# woodenHaptics_v_0_4.net
KiCad netlist of a schematic drawn in EAGLE
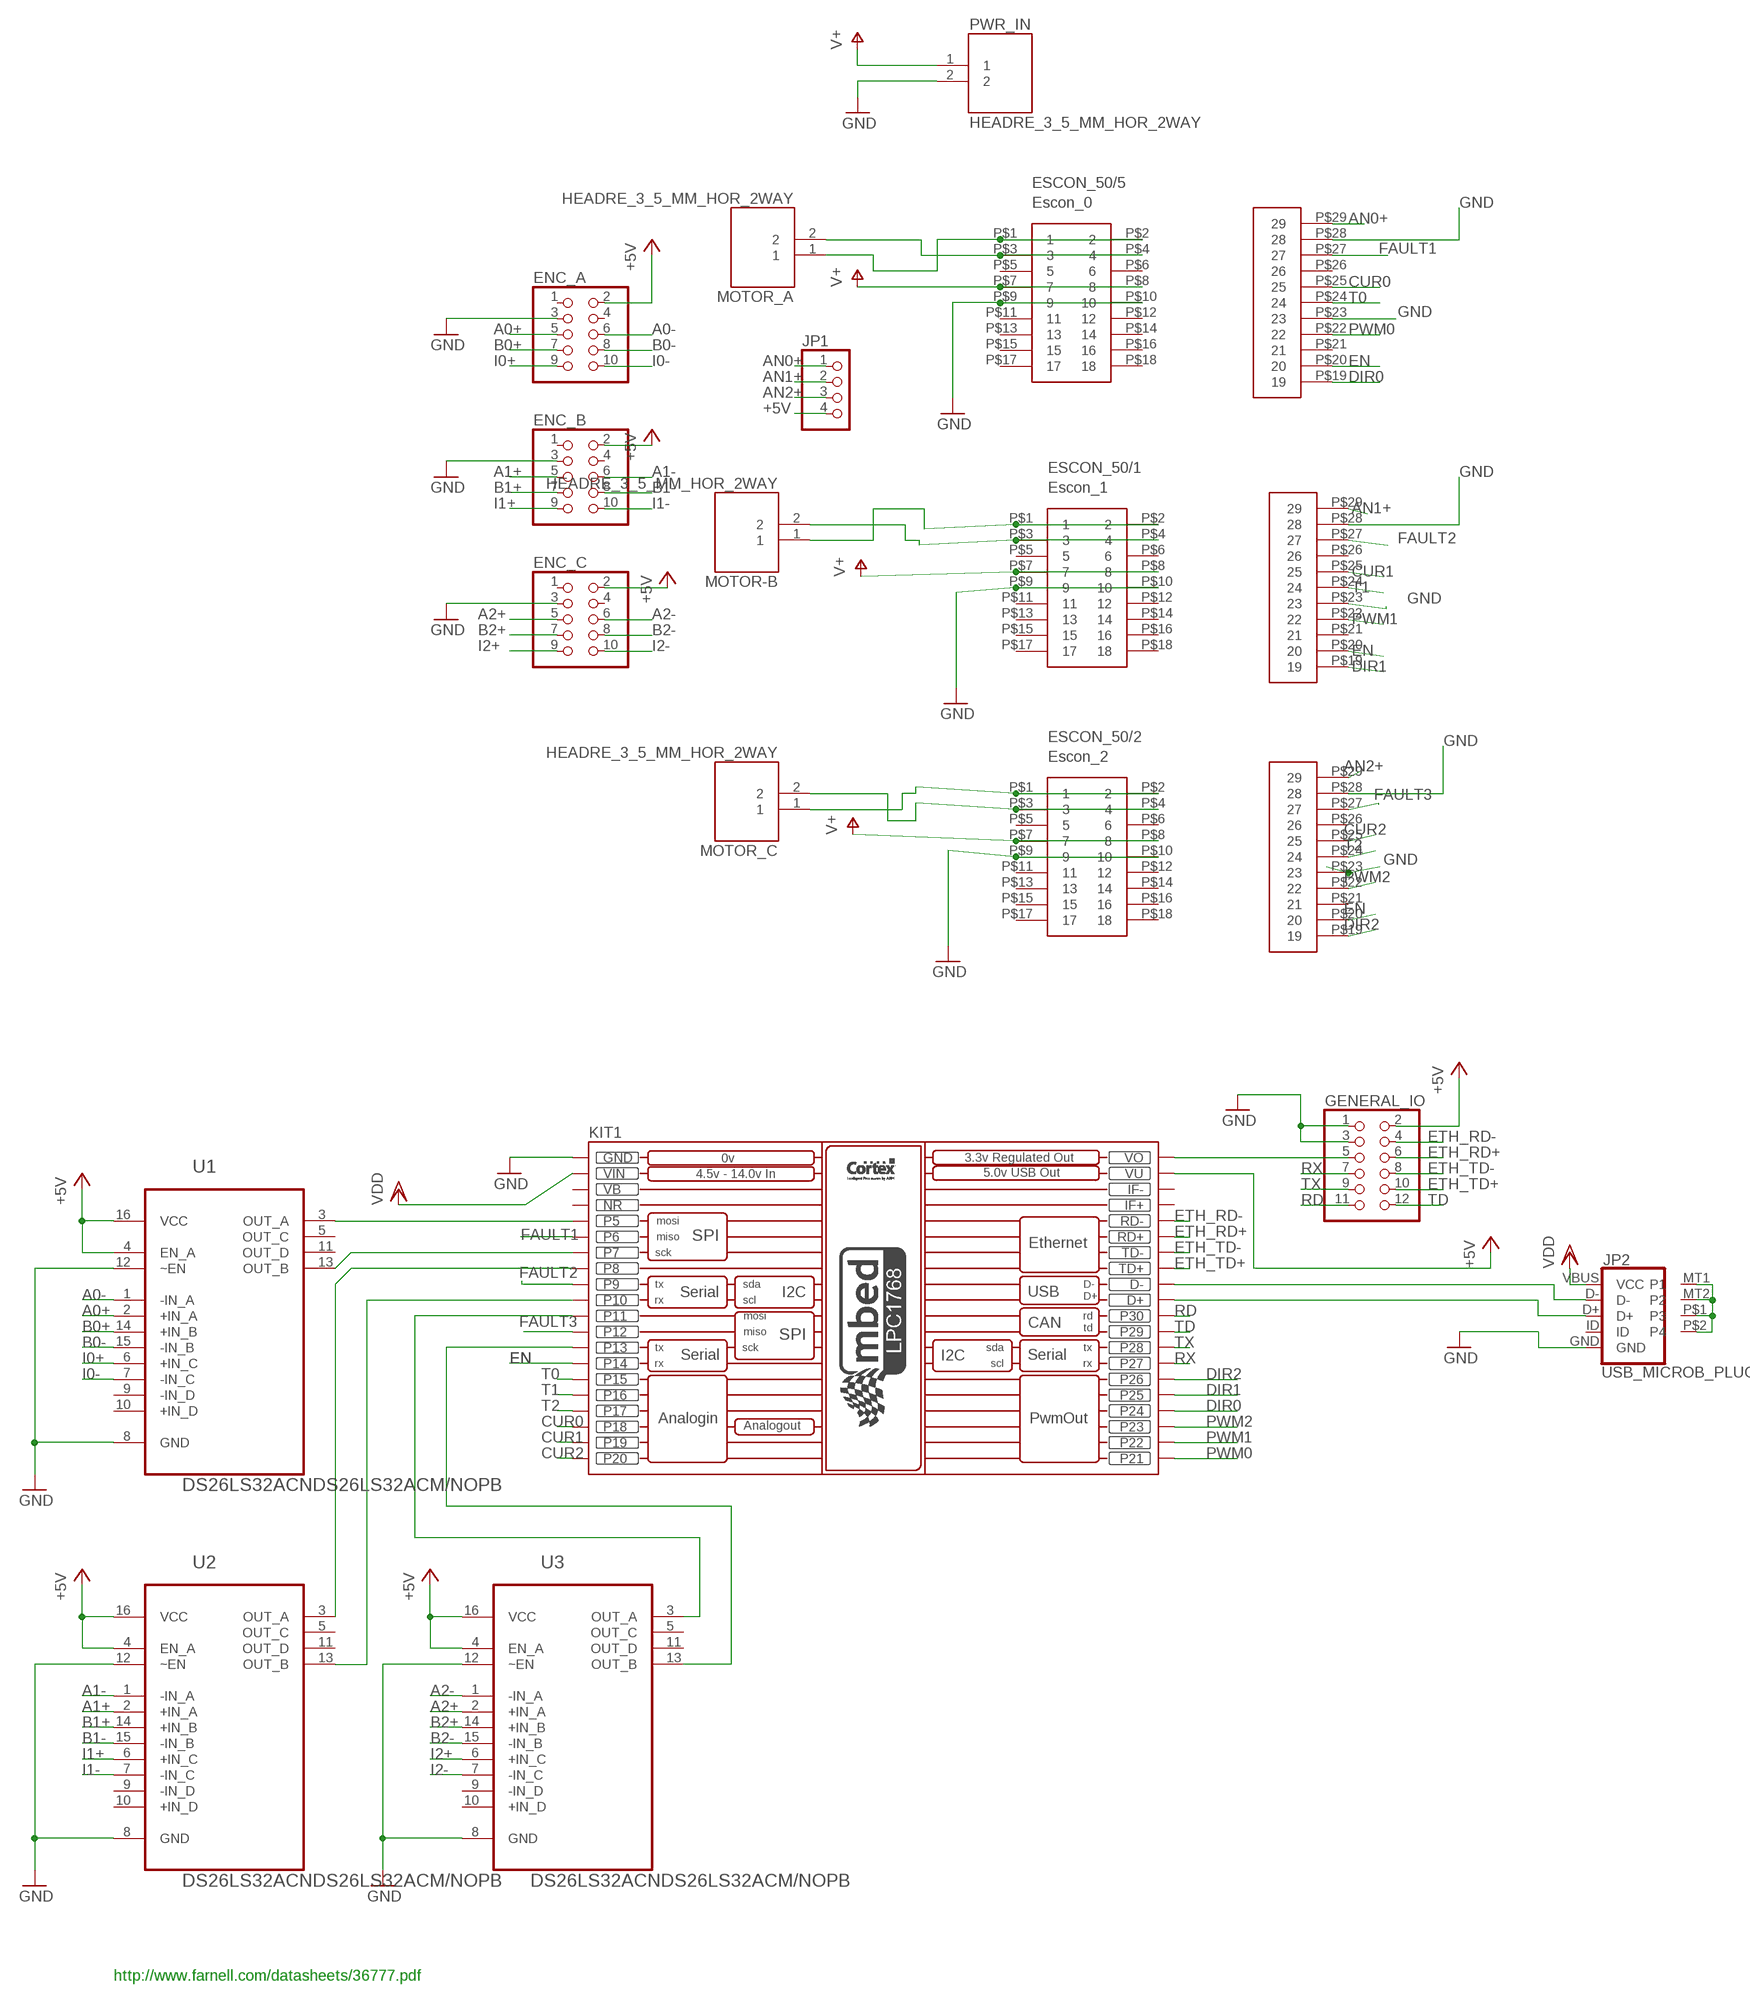
[diagram p0: schematic, sheet 1]

(export (version "E")
  (design (tool "Eeschema 10.0.6"))
  (components
    (comp (ref "ENC_A")
      (value "PINHD-2X5")
      (footprint "eagle-import:2X05")
      (libsource (lib "eagle-import") (part "PINHD-2X5"))
    )
    (comp (ref "ENC_B")
      (value "PINHD-2X5")
      (footprint "eagle-import:2X05")
      (libsource (lib "eagle-import") (part "PINHD-2X5"))
    )
    (comp (ref "ENC_C")
      (value "PINHD-2X5")
      (footprint "eagle-import:2X05")
      (libsource (lib "eagle-import") (part "PINHD-2X5"))
    )
    (comp (ref "ESCON_50/1")
      (value "Escon_1")
      (footprint "eagle-import:MODULE")
      (libsource (lib "eagle-import") (part "ESCON_MODULE_50/5"))
    )
    (comp (ref "ESCON_50/2")
      (value "Escon_2")
      (footprint "eagle-import:MODULE")
      (libsource (lib "eagle-import") (part "ESCON_MODULE_50/5"))
    )
    (comp (ref "ESCON_50/5")
      (value "Escon_0")
      (footprint "eagle-import:MODULE")
      (libsource (lib "eagle-import") (part "ESCON_MODULE_50/5"))
    )
    (comp (ref "GENERAL_IO")
      (value "PINHD-2X6")
      (footprint "eagle-import:2X06")
      (libsource (lib "eagle-import") (part "PINHD-2X6"))
    )
    (comp (ref "JP1")
      (value "PINHD-1X4")
      (footprint "eagle-import:1X04")
      (libsource (lib "eagle-import") (part "PINHD-1X4"))
    )
    (comp (ref "JP2")
      (value "USB_MICROB_PLUG")
      (footprint "eagle-import:USB-MICROB")
      (libsource (lib "eagle-import") (part "USB_MICROB_PLUG"))
    )
    (comp (ref "KIT1")
      (value "MBED_NXP_LPC1768")
      (footprint "eagle-import:MBED-KIT")
      (libsource (lib "eagle-import") (part "MBED_NXP_LPC1768"))
    )
    (comp (ref "MOTOR-B")
      (value "HEADRE_3_5_MM_HOR_2WAY")
      (footprint "eagle-import:HEADER_3_5MM_HOR_2WAY")
      (libsource (lib "eagle-import") (part "HEADRE_3_5_MM_HOR_2WAY"))
    )
    (comp (ref "MOTOR_A")
      (value "HEADRE_3_5_MM_HOR_2WAY")
      (footprint "eagle-import:HEADER_3_5MM_HOR_2WAY")
      (libsource (lib "eagle-import") (part "HEADRE_3_5_MM_HOR_2WAY"))
    )
    (comp (ref "MOTOR_C")
      (value "HEADRE_3_5_MM_HOR_2WAY")
      (footprint "eagle-import:HEADER_3_5MM_HOR_2WAY")
      (libsource (lib "eagle-import") (part "HEADRE_3_5_MM_HOR_2WAY"))
    )
    (comp (ref "PWR_IN")
      (value "HEADRE_3_5_MM_HOR_2WAY")
      (footprint "eagle-import:HEADER_3_5MM_HOR_2WAY")
      (libsource (lib "eagle-import") (part "HEADRE_3_5_MM_HOR_2WAY"))
    )
    (comp (ref "U1")
      (value "DS26LS32ACNDS26LS32ACM/NOPB")
      (footprint "eagle-import:M16")
      (libsource (lib "eagle-import") (part "DS26LS32ACNDS26LS32ACM/NOPB"))
    )
    (comp (ref "U2")
      (value "DS26LS32ACNDS26LS32ACM/NOPB")
      (footprint "eagle-import:M16")
      (libsource (lib "eagle-import") (part "DS26LS32ACNDS26LS32ACM/NOPB"))
    )
    (comp (ref "U3")
      (value "DS26LS32ACNDS26LS32ACM/NOPB")
      (footprint "eagle-import:M16")
      (libsource (lib "eagle-import") (part "DS26LS32ACNDS26LS32ACM/NOPB"))
    )
  )
  (nets
    (net (code "1") (name "+5V") (class "Default")
      (node (ref "ENC_A") (pin "2") (pinfunction "2_2") (pintype "passive"))
      (node (ref "ENC_B") (pin "2") (pinfunction "2_2") (pintype "passive"))
      (node (ref "ENC_C") (pin "2") (pinfunction "2_2") (pintype "passive"))
      (node (ref "GENERAL_IO") (pin "2") (pinfunction "2_2") (pintype "passive"))
      (node (ref "JP1") (pin "4") (pinfunction "4_4") (pintype "passive"))
      (node (ref "KIT1") (pin "VU") (pinfunction "VU_VU") (pintype "power_in"))
      (node (ref "U1") (pin "16") (pinfunction "VCC_16") (pintype "power_in"))
      (node (ref "U1") (pin "4") (pinfunction "EN_A_4") (pintype "input"))
      (node (ref "U2") (pin "16") (pinfunction "VCC_16") (pintype "power_in"))
      (node (ref "U2") (pin "4") (pinfunction "EN_A_4") (pintype "input"))
      (node (ref "U3") (pin "16") (pinfunction "VCC_16") (pintype "power_in"))
      (node (ref "U3") (pin "4") (pinfunction "EN_A_4") (pintype "input"))
    )
    (net (code "2") (name "/A0+") (class "Default")
      (node (ref "ENC_A") (pin "5") (pinfunction "5_5") (pintype "passive"))
      (node (ref "U1") (pin "2") (pinfunction "+IN_A_2") (pintype "input"))
    )
    (net (code "3") (name "/A0-") (class "Default")
      (node (ref "ENC_A") (pin "6") (pinfunction "6_6") (pintype "passive"))
      (node (ref "U1") (pin "1") (pinfunction "-IN_A_1") (pintype "input"))
    )
    (net (code "4") (name "/A1+") (class "Default")
      (node (ref "ENC_B") (pin "5") (pinfunction "5_5") (pintype "passive"))
      (node (ref "U2") (pin "2") (pinfunction "+IN_A_2") (pintype "input"))
    )
    (net (code "5") (name "/A1-") (class "Default")
      (node (ref "ENC_B") (pin "6") (pinfunction "6_6") (pintype "passive"))
      (node (ref "U2") (pin "1") (pinfunction "-IN_A_1") (pintype "input"))
    )
    (net (code "6") (name "/A2+") (class "Default")
      (node (ref "ENC_C") (pin "5") (pinfunction "5_5") (pintype "passive"))
      (node (ref "U3") (pin "2") (pinfunction "+IN_A_2") (pintype "input"))
    )
    (net (code "7") (name "/A2-") (class "Default")
      (node (ref "ENC_C") (pin "6") (pinfunction "6_6") (pintype "passive"))
      (node (ref "U3") (pin "1") (pinfunction "-IN_A_1") (pintype "input"))
    )
    (net (code "8") (name "/AN0+") (class "Default")
      (node (ref "ESCON_50/5") (pin "P$29") (pinfunction "29_P$29") (pintype "bidirectional"))
      (node (ref "JP1") (pin "1") (pinfunction "1_1") (pintype "passive"))
    )
    (net (code "9") (name "/AN1+") (class "Default")
      (node (ref "ESCON_50/1") (pin "P$29") (pinfunction "29_P$29") (pintype "bidirectional"))
      (node (ref "JP1") (pin "2") (pinfunction "2_2") (pintype "passive"))
    )
    (net (code "10") (name "/AN2+") (class "Default")
      (node (ref "ESCON_50/2") (pin "P$29") (pinfunction "29_P$29") (pintype "bidirectional"))
      (node (ref "JP1") (pin "3") (pinfunction "3_3") (pintype "passive"))
    )
    (net (code "11") (name "/B0+") (class "Default")
      (node (ref "ENC_A") (pin "7") (pinfunction "7_7") (pintype "passive"))
      (node (ref "U1") (pin "14") (pinfunction "+IN_B_14") (pintype "input"))
    )
    (net (code "12") (name "/B0-") (class "Default")
      (node (ref "ENC_A") (pin "8") (pinfunction "8_8") (pintype "passive"))
      (node (ref "U1") (pin "15") (pinfunction "-IN_B_15") (pintype "input"))
    )
    (net (code "13") (name "/B1+") (class "Default")
      (node (ref "ENC_B") (pin "7") (pinfunction "7_7") (pintype "passive"))
      (node (ref "U2") (pin "14") (pinfunction "+IN_B_14") (pintype "input"))
    )
    (net (code "14") (name "/B1-") (class "Default")
      (node (ref "ENC_B") (pin "8") (pinfunction "8_8") (pintype "passive"))
      (node (ref "U2") (pin "15") (pinfunction "-IN_B_15") (pintype "input"))
    )
    (net (code "15") (name "/B2+") (class "Default")
      (node (ref "ENC_C") (pin "7") (pinfunction "7_7") (pintype "passive"))
      (node (ref "U3") (pin "14") (pinfunction "+IN_B_14") (pintype "input"))
    )
    (net (code "16") (name "/B2-") (class "Default")
      (node (ref "ENC_C") (pin "8") (pinfunction "8_8") (pintype "passive"))
      (node (ref "U3") (pin "15") (pinfunction "-IN_B_15") (pintype "input"))
    )
    (net (code "17") (name "/CUR0") (class "Default")
      (node (ref "ESCON_50/5") (pin "P$25") (pinfunction "25_P$25") (pintype "bidirectional"))
      (node (ref "KIT1") (pin "P$18") (pinfunction "P18_P$18") (pintype "bidirectional"))
    )
    (net (code "18") (name "/CUR1") (class "Default")
      (node (ref "ESCON_50/1") (pin "P$25") (pinfunction "25_P$25") (pintype "bidirectional"))
      (node (ref "KIT1") (pin "P$19") (pinfunction "P19_P$19") (pintype "bidirectional"))
    )
    (net (code "19") (name "/CUR2") (class "Default")
      (node (ref "ESCON_50/2") (pin "P$25") (pinfunction "25_P$25") (pintype "bidirectional"))
      (node (ref "KIT1") (pin "P$20") (pinfunction "P20_P$20") (pintype "bidirectional"))
    )
    (net (code "20") (name "/DIR0") (class "Default")
      (node (ref "ESCON_50/5") (pin "P$19") (pinfunction "19_P$19") (pintype "bidirectional"))
      (node (ref "KIT1") (pin "P$24") (pinfunction "P24_P$24") (pintype "bidirectional"))
    )
    (net (code "21") (name "/DIR1") (class "Default")
      (node (ref "ESCON_50/1") (pin "P$19") (pinfunction "19_P$19") (pintype "bidirectional"))
      (node (ref "KIT1") (pin "P$25") (pinfunction "P25_P$25") (pintype "bidirectional"))
    )
    (net (code "22") (name "/DIR2") (class "Default")
      (node (ref "ESCON_50/2") (pin "P$19") (pinfunction "19_P$19") (pintype "bidirectional"))
      (node (ref "KIT1") (pin "P$26") (pinfunction "P26_P$26") (pintype "bidirectional"))
    )
    (net (code "23") (name "/EN") (class "Default")
      (node (ref "ESCON_50/1") (pin "P$20") (pinfunction "20_P$20") (pintype "bidirectional"))
      (node (ref "ESCON_50/2") (pin "P$20") (pinfunction "20_P$20") (pintype "bidirectional"))
      (node (ref "ESCON_50/5") (pin "P$20") (pinfunction "20_P$20") (pintype "bidirectional"))
      (node (ref "KIT1") (pin "P$14") (pinfunction "P14_P$14") (pintype "bidirectional"))
    )
    (net (code "24") (name "/ETH_RD+") (class "Default")
      (node (ref "GENERAL_IO") (pin "6") (pinfunction "6_6") (pintype "passive"))
      (node (ref "KIT1") (pin "RD+") (pinfunction "RD+_RD+") (pintype "bidirectional"))
    )
    (net (code "25") (name "/ETH_RD-") (class "Default")
      (node (ref "GENERAL_IO") (pin "4") (pinfunction "4_4") (pintype "passive"))
      (node (ref "KIT1") (pin "RD-") (pinfunction "RD-_RD-") (pintype "bidirectional"))
    )
    (net (code "26") (name "/ETH_TD+") (class "Default")
      (node (ref "GENERAL_IO") (pin "10") (pinfunction "10_10") (pintype "passive"))
      (node (ref "KIT1") (pin "TD+") (pinfunction "TD+_TD+") (pintype "bidirectional"))
    )
    (net (code "27") (name "/ETH_TD-") (class "Default")
      (node (ref "GENERAL_IO") (pin "8") (pinfunction "8_8") (pintype "passive"))
      (node (ref "KIT1") (pin "TD-") (pinfunction "TD-_TD-") (pintype "bidirectional"))
    )
    (net (code "28") (name "/FAULT1") (class "Default")
      (node (ref "ESCON_50/5") (pin "P$27") (pinfunction "27_P$27") (pintype "bidirectional"))
      (node (ref "KIT1") (pin "P$6") (pinfunction "P6_P$6") (pintype "bidirectional"))
    )
    (net (code "29") (name "/FAULT2") (class "Default")
      (node (ref "ESCON_50/1") (pin "P$27") (pinfunction "27_P$27") (pintype "bidirectional"))
      (node (ref "KIT1") (pin "P$9") (pinfunction "P9_P$9") (pintype "bidirectional"))
    )
    (net (code "30") (name "/FAULT3") (class "Default")
      (node (ref "ESCON_50/2") (pin "P$27") (pinfunction "27_P$27") (pintype "bidirectional"))
      (node (ref "KIT1") (pin "P$12") (pinfunction "P12_P$12") (pintype "bidirectional"))
    )
    (net (code "31") (name "/I0+") (class "Default")
      (node (ref "ENC_A") (pin "9") (pinfunction "9_9") (pintype "passive"))
      (node (ref "U1") (pin "6") (pinfunction "+IN_C_6") (pintype "input"))
    )
    (net (code "32") (name "/I0-") (class "Default")
      (node (ref "ENC_A") (pin "10") (pinfunction "10_10") (pintype "passive"))
      (node (ref "U1") (pin "7") (pinfunction "-IN_C_7") (pintype "input"))
    )
    (net (code "33") (name "/I1+") (class "Default")
      (node (ref "ENC_B") (pin "9") (pinfunction "9_9") (pintype "passive"))
      (node (ref "U2") (pin "6") (pinfunction "+IN_C_6") (pintype "input"))
    )
    (net (code "34") (name "/I1-") (class "Default")
      (node (ref "ENC_B") (pin "10") (pinfunction "10_10") (pintype "passive"))
      (node (ref "U2") (pin "7") (pinfunction "-IN_C_7") (pintype "input"))
    )
    (net (code "35") (name "/I2+") (class "Default")
      (node (ref "ENC_C") (pin "9") (pinfunction "9_9") (pintype "passive"))
      (node (ref "U3") (pin "6") (pinfunction "+IN_C_6") (pintype "input"))
    )
    (net (code "36") (name "/I2-") (class "Default")
      (node (ref "ENC_C") (pin "10") (pinfunction "10_10") (pintype "passive"))
      (node (ref "U3") (pin "7") (pinfunction "-IN_C_7") (pintype "input"))
    )
    (net (code "37") (name "/NR") (class "Default")
      (node (ref "KIT1") (pin "NR") (pinfunction "NR_NR") (pintype "power_in"))
    )
    (net (code "38") (name "/PWM0") (class "Default")
      (node (ref "ESCON_50/5") (pin "P$22") (pinfunction "22_P$22") (pintype "bidirectional"))
      (node (ref "KIT1") (pin "P$21") (pinfunction "P21_P$21") (pintype "bidirectional"))
    )
    (net (code "39") (name "/PWM1") (class "Default")
      (node (ref "ESCON_50/1") (pin "P$22") (pinfunction "22_P$22") (pintype "bidirectional"))
      (node (ref "KIT1") (pin "P$22") (pinfunction "P22_P$22") (pintype "bidirectional"))
    )
    (net (code "40") (name "/PWM2") (class "Default")
      (node (ref "ESCON_50/2") (pin "P$22") (pinfunction "22_P$22") (pintype "bidirectional"))
      (node (ref "KIT1") (pin "P$23") (pinfunction "P23_P$23") (pintype "bidirectional"))
    )
    (net (code "41") (name "/RD") (class "Default")
      (node (ref "GENERAL_IO") (pin "11") (pinfunction "11_11") (pintype "passive"))
      (node (ref "KIT1") (pin "P$30") (pinfunction "P30_P$30") (pintype "bidirectional"))
    )
    (net (code "42") (name "/RX") (class "Default")
      (node (ref "GENERAL_IO") (pin "7") (pinfunction "7_7") (pintype "passive"))
      (node (ref "KIT1") (pin "P$27") (pinfunction "P27_P$27") (pintype "bidirectional"))
    )
    (net (code "43") (name "/T0") (class "Default")
      (node (ref "ESCON_50/5") (pin "P$24") (pinfunction "24_P$24") (pintype "bidirectional"))
      (node (ref "KIT1") (pin "P$15") (pinfunction "P15_P$15") (pintype "bidirectional"))
    )
    (net (code "44") (name "/T1") (class "Default")
      (node (ref "ESCON_50/1") (pin "P$24") (pinfunction "24_P$24") (pintype "bidirectional"))
      (node (ref "KIT1") (pin "P$16") (pinfunction "P16_P$16") (pintype "bidirectional"))
    )
    (net (code "45") (name "/T2") (class "Default")
      (node (ref "ESCON_50/2") (pin "P$24") (pinfunction "24_P$24") (pintype "bidirectional"))
      (node (ref "KIT1") (pin "P$17") (pinfunction "P17_P$17") (pintype "bidirectional"))
    )
    (net (code "46") (name "/TD") (class "Default")
      (node (ref "GENERAL_IO") (pin "12") (pinfunction "12_12") (pintype "passive"))
      (node (ref "KIT1") (pin "P$29") (pinfunction "P29_P$29") (pintype "bidirectional"))
    )
    (net (code "47") (name "/TX") (class "Default")
      (node (ref "GENERAL_IO") (pin "9") (pinfunction "9_9") (pintype "passive"))
      (node (ref "KIT1") (pin "P$28") (pinfunction "P28_P$28") (pintype "bidirectional"))
    )
    (net (code "48") (name "/VB") (class "Default")
      (node (ref "KIT1") (pin "VB") (pinfunction "VB_VB") (pintype "power_in"))
    )
    (net (code "49") (name "GND") (class "Default")
      (node (ref "ENC_A") (pin "3") (pinfunction "3_3") (pintype "passive"))
      (node (ref "ENC_B") (pin "3") (pinfunction "3_3") (pintype "passive"))
      (node (ref "ENC_C") (pin "3") (pinfunction "3_3") (pintype "passive"))
      (node (ref "ESCON_50/1") (pin "P$10") (pinfunction "10_P$10") (pintype "power_in"))
      (node (ref "ESCON_50/1") (pin "P$23") (pinfunction "23_P$23") (pintype "bidirectional"))
      (node (ref "ESCON_50/1") (pin "P$28") (pinfunction "28_P$28") (pintype "bidirectional"))
      (node (ref "ESCON_50/1") (pin "P$9") (pinfunction "9_P$9") (pintype "power_in"))
      (node (ref "ESCON_50/2") (pin "P$10") (pinfunction "10_P$10") (pintype "power_in"))
      (node (ref "ESCON_50/2") (pin "P$23") (pinfunction "23_P$23") (pintype "bidirectional"))
      (node (ref "ESCON_50/2") (pin "P$28") (pinfunction "28_P$28") (pintype "bidirectional"))
      (node (ref "ESCON_50/2") (pin "P$9") (pinfunction "9_P$9") (pintype "power_in"))
      (node (ref "ESCON_50/5") (pin "P$10") (pinfunction "10_P$10") (pintype "power_in"))
      (node (ref "ESCON_50/5") (pin "P$23") (pinfunction "23_P$23") (pintype "bidirectional"))
      (node (ref "ESCON_50/5") (pin "P$28") (pinfunction "28_P$28") (pintype "bidirectional"))
      (node (ref "ESCON_50/5") (pin "P$9") (pinfunction "9_P$9") (pintype "power_in"))
      (node (ref "GENERAL_IO") (pin "1") (pinfunction "1_1") (pintype "passive"))
      (node (ref "GENERAL_IO") (pin "3") (pinfunction "3_3") (pintype "passive"))
      (node (ref "JP2") (pin "GND") (pinfunction "GND_GND") (pintype "bidirectional"))
      (node (ref "KIT1") (pin "GND") (pinfunction "GND_GND") (pintype "power_in"))
      (node (ref "PWR_IN") (pin "2") (pinfunction "2_2") (pintype "bidirectional"))
      (node (ref "U1") (pin "12") (pinfunction "~{EN}_12") (pintype "input"))
      (node (ref "U1") (pin "8") (pinfunction "GND_8") (pintype "passive"))
      (node (ref "U2") (pin "12") (pinfunction "~{EN}_12") (pintype "input"))
      (node (ref "U2") (pin "8") (pinfunction "GND_8") (pintype "passive"))
      (node (ref "U3") (pin "12") (pinfunction "~{EN}_12") (pintype "input"))
      (node (ref "U3") (pin "8") (pinfunction "GND_8") (pintype "passive"))
    )
    (net (code "50") (name "Net-(ESCON_50/1-1)") (class "Default")
      (node (ref "ESCON_50/1") (pin "P$1") (pinfunction "1_P$1") (pintype "bidirectional"))
      (node (ref "ESCON_50/1") (pin "P$2") (pinfunction "2_P$2") (pintype "bidirectional"))
      (node (ref "MOTOR-B") (pin "1") (pinfunction "1_1") (pintype "bidirectional"))
    )
    (net (code "51") (name "Net-(ESCON_50/1-3)") (class "Default")
      (node (ref "ESCON_50/1") (pin "P$3") (pinfunction "3_P$3") (pintype "bidirectional"))
      (node (ref "ESCON_50/1") (pin "P$4") (pinfunction "4_P$4") (pintype "bidirectional"))
      (node (ref "MOTOR-B") (pin "2") (pinfunction "2_2") (pintype "bidirectional"))
    )
    (net (code "52") (name "Net-(ESCON_50/2-1)") (class "Default")
      (node (ref "ESCON_50/2") (pin "P$1") (pinfunction "1_P$1") (pintype "bidirectional"))
      (node (ref "ESCON_50/2") (pin "P$2") (pinfunction "2_P$2") (pintype "bidirectional"))
      (node (ref "MOTOR_C") (pin "1") (pinfunction "1_1") (pintype "bidirectional"))
    )
    (net (code "53") (name "Net-(ESCON_50/2-3)") (class "Default")
      (node (ref "ESCON_50/2") (pin "P$3") (pinfunction "3_P$3") (pintype "bidirectional"))
      (node (ref "ESCON_50/2") (pin "P$4") (pinfunction "4_P$4") (pintype "bidirectional"))
      (node (ref "MOTOR_C") (pin "2") (pinfunction "2_2") (pintype "bidirectional"))
    )
    (net (code "54") (name "Net-(ESCON_50/5-1)") (class "Default")
      (node (ref "ESCON_50/5") (pin "P$1") (pinfunction "1_P$1") (pintype "bidirectional"))
      (node (ref "ESCON_50/5") (pin "P$2") (pinfunction "2_P$2") (pintype "bidirectional"))
      (node (ref "MOTOR_A") (pin "1") (pinfunction "1_1") (pintype "bidirectional"))
    )
    (net (code "55") (name "Net-(ESCON_50/5-3)") (class "Default")
      (node (ref "ESCON_50/5") (pin "P$3") (pinfunction "3_P$3") (pintype "bidirectional"))
      (node (ref "ESCON_50/5") (pin "P$4") (pinfunction "4_P$4") (pintype "bidirectional"))
      (node (ref "MOTOR_A") (pin "2") (pinfunction "2_2") (pintype "bidirectional"))
    )
    (net (code "56") (name "Net-(JP2-P1)") (class "Default")
      (node (ref "JP2") (pin "MT1") (pinfunction "P1_MT1") (pintype "bidirectional"))
      (node (ref "JP2") (pin "MT2") (pinfunction "P2_MT2") (pintype "bidirectional"))
      (node (ref "JP2") (pin "P$1") (pinfunction "P3_P$1") (pintype "bidirectional"))
      (node (ref "JP2") (pin "P$2") (pinfunction "P4_P$2") (pintype "bidirectional"))
    )
    (net (code "57") (name "Net-(JP2-PadD+)") (class "Default")
      (node (ref "JP2") (pin "D+") (pinfunction "D+_D+") (pintype "bidirectional"))
      (node (ref "KIT1") (pin "D+") (pinfunction "D+_D+") (pintype "bidirectional"))
    )
    (net (code "58") (name "Net-(JP2-PadD-)") (class "Default")
      (node (ref "JP2") (pin "D-") (pinfunction "D-_D-") (pintype "bidirectional"))
      (node (ref "KIT1") (pin "D-") (pinfunction "D-_D-") (pintype "bidirectional"))
    )
    (net (code "59") (name "Net-(KIT1-P5)") (class "Default")
      (node (ref "KIT1") (pin "P$5") (pinfunction "P5_P$5") (pintype "bidirectional"))
      (node (ref "U1") (pin "3") (pinfunction "OUT_A_3") (pintype "output"))
    )
    (net (code "60") (name "Net-(KIT1-P7)") (class "Default")
      (node (ref "KIT1") (pin "P$7") (pinfunction "P7_P$7") (pintype "bidirectional"))
      (node (ref "U1") (pin "13") (pinfunction "OUT_B_13") (pintype "output"))
    )
    (net (code "61") (name "Net-(KIT1-P8)") (class "Default")
      (node (ref "KIT1") (pin "P$8") (pinfunction "P8_P$8") (pintype "bidirectional"))
      (node (ref "U2") (pin "3") (pinfunction "OUT_A_3") (pintype "output"))
    )
    (net (code "62") (name "Net-(KIT1-P10)") (class "Default")
      (node (ref "KIT1") (pin "P$10") (pinfunction "P10_P$10") (pintype "bidirectional"))
      (node (ref "U2") (pin "13") (pinfunction "OUT_B_13") (pintype "output"))
    )
    (net (code "63") (name "Net-(KIT1-P11)") (class "Default")
      (node (ref "KIT1") (pin "P$11") (pinfunction "P11_P$11") (pintype "bidirectional"))
      (node (ref "U3") (pin "3") (pinfunction "OUT_A_3") (pintype "output"))
    )
    (net (code "64") (name "Net-(KIT1-P13)") (class "Default")
      (node (ref "KIT1") (pin "P$13") (pinfunction "P13_P$13") (pintype "bidirectional"))
      (node (ref "U3") (pin "13") (pinfunction "OUT_B_13") (pintype "output"))
    )
    (net (code "65") (name "Net-(KIT1-VO)") (class "Default")
      (node (ref "GENERAL_IO") (pin "5") (pinfunction "5_5") (pintype "passive"))
      (node (ref "KIT1") (pin "VOUT") (pinfunction "VO_VOUT") (pintype "power_in"))
    )
    (net (code "66") (name "V+") (class "Default")
      (node (ref "ESCON_50/1") (pin "P$7") (pinfunction "7_P$7") (pintype "power_in"))
      (node (ref "ESCON_50/1") (pin "P$8") (pinfunction "8_P$8") (pintype "power_in"))
      (node (ref "ESCON_50/2") (pin "P$7") (pinfunction "7_P$7") (pintype "power_in"))
      (node (ref "ESCON_50/2") (pin "P$8") (pinfunction "8_P$8") (pintype "power_in"))
      (node (ref "ESCON_50/5") (pin "P$7") (pinfunction "7_P$7") (pintype "power_in"))
      (node (ref "ESCON_50/5") (pin "P$8") (pinfunction "8_P$8") (pintype "power_in"))
      (node (ref "PWR_IN") (pin "1") (pinfunction "1_1") (pintype "bidirectional"))
    )
    (net (code "67") (name "VDD") (class "Default")
      (node (ref "JP2") (pin "VBUS") (pinfunction "VCC_VBUS") (pintype "bidirectional"))
      (node (ref "KIT1") (pin "VIN") (pinfunction "VIN_VIN") (pintype "power_in"))
    )
    (net (code "68") (name "unconnected-(ENC_A-Pad1)") (class "Default")
      (node (ref "ENC_A") (pin "1") (pinfunction "1_1") (pintype "passive"))
    )
    (net (code "69") (name "unconnected-(ENC_A-Pad4)") (class "Default")
      (node (ref "ENC_A") (pin "4") (pinfunction "4_4") (pintype "passive"))
    )
    (net (code "70") (name "unconnected-(ENC_B-Pad1)") (class "Default")
      (node (ref "ENC_B") (pin "1") (pinfunction "1_1") (pintype "passive"))
    )
    (net (code "71") (name "unconnected-(ENC_B-Pad4)") (class "Default")
      (node (ref "ENC_B") (pin "4") (pinfunction "4_4") (pintype "passive"))
    )
    (net (code "72") (name "unconnected-(ENC_C-Pad1)") (class "Default")
      (node (ref "ENC_C") (pin "1") (pinfunction "1_1") (pintype "passive"))
    )
    (net (code "73") (name "unconnected-(ENC_C-Pad4)") (class "Default")
      (node (ref "ENC_C") (pin "4") (pinfunction "4_4") (pintype "passive"))
    )
    (net (code "74") (name "unconnected-(ESCON_50/1-5-PadP$5)") (class "Default")
      (node (ref "ESCON_50/1") (pin "P$5") (pinfunction "5_P$5") (pintype "bidirectional"))
    )
    (net (code "75") (name "unconnected-(ESCON_50/1-6-PadP$6)") (class "Default")
      (node (ref "ESCON_50/1") (pin "P$6") (pinfunction "6_P$6") (pintype "bidirectional"))
    )
    (net (code "76") (name "unconnected-(ESCON_50/1-11-PadP$11)") (class "Default")
      (node (ref "ESCON_50/1") (pin "P$11") (pinfunction "11_P$11") (pintype "bidirectional"))
    )
    (net (code "77") (name "unconnected-(ESCON_50/1-12-PadP$12)") (class "Default")
      (node (ref "ESCON_50/1") (pin "P$12") (pinfunction "12_P$12") (pintype "bidirectional"))
    )
    (net (code "78") (name "unconnected-(ESCON_50/1-13-PadP$13)") (class "Default")
      (node (ref "ESCON_50/1") (pin "P$13") (pinfunction "13_P$13") (pintype "bidirectional"))
    )
    (net (code "79") (name "unconnected-(ESCON_50/1-14-PadP$14)") (class "Default")
      (node (ref "ESCON_50/1") (pin "P$14") (pinfunction "14_P$14") (pintype "bidirectional"))
    )
    (net (code "80") (name "unconnected-(ESCON_50/1-15-PadP$15)") (class "Default")
      (node (ref "ESCON_50/1") (pin "P$15") (pinfunction "15_P$15") (pintype "bidirectional"))
    )
    (net (code "81") (name "unconnected-(ESCON_50/1-16-PadP$16)") (class "Default")
      (node (ref "ESCON_50/1") (pin "P$16") (pinfunction "16_P$16") (pintype "bidirectional"))
    )
    (net (code "82") (name "unconnected-(ESCON_50/1-17-PadP$17)") (class "Default")
      (node (ref "ESCON_50/1") (pin "P$17") (pinfunction "17_P$17") (pintype "bidirectional"))
    )
    (net (code "83") (name "unconnected-(ESCON_50/1-18-PadP$18)") (class "Default")
      (node (ref "ESCON_50/1") (pin "P$18") (pinfunction "18_P$18") (pintype "bidirectional"))
    )
    (net (code "84") (name "unconnected-(ESCON_50/1-21-PadP$21)") (class "Default")
      (node (ref "ESCON_50/1") (pin "P$21") (pinfunction "21_P$21") (pintype "bidirectional"))
    )
    (net (code "85") (name "unconnected-(ESCON_50/1-26-PadP$26)") (class "Default")
      (node (ref "ESCON_50/1") (pin "P$26") (pinfunction "26_P$26") (pintype "bidirectional"))
    )
    (net (code "86") (name "unconnected-(ESCON_50/2-5-PadP$5)") (class "Default")
      (node (ref "ESCON_50/2") (pin "P$5") (pinfunction "5_P$5") (pintype "bidirectional"))
    )
    (net (code "87") (name "unconnected-(ESCON_50/2-6-PadP$6)") (class "Default")
      (node (ref "ESCON_50/2") (pin "P$6") (pinfunction "6_P$6") (pintype "bidirectional"))
    )
    (net (code "88") (name "unconnected-(ESCON_50/2-11-PadP$11)") (class "Default")
      (node (ref "ESCON_50/2") (pin "P$11") (pinfunction "11_P$11") (pintype "bidirectional"))
    )
    (net (code "89") (name "unconnected-(ESCON_50/2-12-PadP$12)") (class "Default")
      (node (ref "ESCON_50/2") (pin "P$12") (pinfunction "12_P$12") (pintype "bidirectional"))
    )
    (net (code "90") (name "unconnected-(ESCON_50/2-13-PadP$13)") (class "Default")
      (node (ref "ESCON_50/2") (pin "P$13") (pinfunction "13_P$13") (pintype "bidirectional"))
    )
    (net (code "91") (name "unconnected-(ESCON_50/2-14-PadP$14)") (class "Default")
      (node (ref "ESCON_50/2") (pin "P$14") (pinfunction "14_P$14") (pintype "bidirectional"))
    )
    (net (code "92") (name "unconnected-(ESCON_50/2-15-PadP$15)") (class "Default")
      (node (ref "ESCON_50/2") (pin "P$15") (pinfunction "15_P$15") (pintype "bidirectional"))
    )
    (net (code "93") (name "unconnected-(ESCON_50/2-16-PadP$16)") (class "Default")
      (node (ref "ESCON_50/2") (pin "P$16") (pinfunction "16_P$16") (pintype "bidirectional"))
    )
    (net (code "94") (name "unconnected-(ESCON_50/2-17-PadP$17)") (class "Default")
      (node (ref "ESCON_50/2") (pin "P$17") (pinfunction "17_P$17") (pintype "bidirectional"))
    )
    (net (code "95") (name "unconnected-(ESCON_50/2-18-PadP$18)") (class "Default")
      (node (ref "ESCON_50/2") (pin "P$18") (pinfunction "18_P$18") (pintype "bidirectional"))
    )
    (net (code "96") (name "unconnected-(ESCON_50/2-21-PadP$21)") (class "Default")
      (node (ref "ESCON_50/2") (pin "P$21") (pinfunction "21_P$21") (pintype "bidirectional"))
    )
    (net (code "97") (name "unconnected-(ESCON_50/2-26-PadP$26)") (class "Default")
      (node (ref "ESCON_50/2") (pin "P$26") (pinfunction "26_P$26") (pintype "bidirectional"))
    )
    (net (code "98") (name "unconnected-(ESCON_50/5-5-PadP$5)") (class "Default")
      (node (ref "ESCON_50/5") (pin "P$5") (pinfunction "5_P$5") (pintype "bidirectional"))
    )
    (net (code "99") (name "unconnected-(ESCON_50/5-6-PadP$6)") (class "Default")
      (node (ref "ESCON_50/5") (pin "P$6") (pinfunction "6_P$6") (pintype "bidirectional"))
    )
    (net (code "100") (name "unconnected-(ESCON_50/5-11-PadP$11)") (class "Default")
      (node (ref "ESCON_50/5") (pin "P$11") (pinfunction "11_P$11") (pintype "bidirectional"))
    )
    (net (code "101") (name "unconnected-(ESCON_50/5-12-PadP$12)") (class "Default")
      (node (ref "ESCON_50/5") (pin "P$12") (pinfunction "12_P$12") (pintype "bidirectional"))
    )
    (net (code "102") (name "unconnected-(ESCON_50/5-13-PadP$13)") (class "Default")
      (node (ref "ESCON_50/5") (pin "P$13") (pinfunction "13_P$13") (pintype "bidirectional"))
    )
    (net (code "103") (name "unconnected-(ESCON_50/5-14-PadP$14)") (class "Default")
      (node (ref "ESCON_50/5") (pin "P$14") (pinfunction "14_P$14") (pintype "bidirectional"))
    )
    (net (code "104") (name "unconnected-(ESCON_50/5-15-PadP$15)") (class "Default")
      (node (ref "ESCON_50/5") (pin "P$15") (pinfunction "15_P$15") (pintype "bidirectional"))
    )
    (net (code "105") (name "unconnected-(ESCON_50/5-16-PadP$16)") (class "Default")
      (node (ref "ESCON_50/5") (pin "P$16") (pinfunction "16_P$16") (pintype "bidirectional"))
    )
    (net (code "106") (name "unconnected-(ESCON_50/5-17-PadP$17)") (class "Default")
      (node (ref "ESCON_50/5") (pin "P$17") (pinfunction "17_P$17") (pintype "bidirectional"))
    )
    (net (code "107") (name "unconnected-(ESCON_50/5-18-PadP$18)") (class "Default")
      (node (ref "ESCON_50/5") (pin "P$18") (pinfunction "18_P$18") (pintype "bidirectional"))
    )
    (net (code "108") (name "unconnected-(ESCON_50/5-21-PadP$21)") (class "Default")
      (node (ref "ESCON_50/5") (pin "P$21") (pinfunction "21_P$21") (pintype "bidirectional"))
    )
    (net (code "109") (name "unconnected-(ESCON_50/5-26-PadP$26)") (class "Default")
      (node (ref "ESCON_50/5") (pin "P$26") (pinfunction "26_P$26") (pintype "bidirectional"))
    )
    (net (code "110") (name "unconnected-(JP2-PadID)") (class "Default")
      (node (ref "JP2") (pin "ID") (pinfunction "ID_ID") (pintype "bidirectional"))
    )
    (net (code "111") (name "unconnected-(KIT1-PadIF+)") (class "Default")
      (node (ref "KIT1") (pin "IF+") (pinfunction "IF+_IF+") (pintype "bidirectional"))
    )
    (net (code "112") (name "unconnected-(KIT1-PadIF-)") (class "Default")
      (node (ref "KIT1") (pin "IF-") (pinfunction "IF-_IF-") (pintype "bidirectional"))
    )
    (net (code "113") (name "unconnected-(U1-+IN_D-Pad10)") (class "Default")
      (node (ref "U1") (pin "10") (pinfunction "+IN_D_10") (pintype "input"))
    )
    (net (code "114") (name "unconnected-(U1--IN_D-Pad9)") (class "Default")
      (node (ref "U1") (pin "9") (pinfunction "-IN_D_9") (pintype "input"))
    )
    (net (code "115") (name "unconnected-(U1-OUT_C-Pad5)") (class "Default")
      (node (ref "U1") (pin "5") (pinfunction "OUT_C_5") (pintype "output"))
    )
    (net (code "116") (name "unconnected-(U1-OUT_D-Pad11)") (class "Default")
      (node (ref "U1") (pin "11") (pinfunction "OUT_D_11") (pintype "output"))
    )
    (net (code "117") (name "unconnected-(U2-+IN_D-Pad10)") (class "Default")
      (node (ref "U2") (pin "10") (pinfunction "+IN_D_10") (pintype "input"))
    )
    (net (code "118") (name "unconnected-(U2--IN_D-Pad9)") (class "Default")
      (node (ref "U2") (pin "9") (pinfunction "-IN_D_9") (pintype "input"))
    )
    (net (code "119") (name "unconnected-(U2-OUT_C-Pad5)") (class "Default")
      (node (ref "U2") (pin "5") (pinfunction "OUT_C_5") (pintype "output"))
    )
    (net (code "120") (name "unconnected-(U2-OUT_D-Pad11)") (class "Default")
      (node (ref "U2") (pin "11") (pinfunction "OUT_D_11") (pintype "output"))
    )
    (net (code "121") (name "unconnected-(U3-+IN_D-Pad10)") (class "Default")
      (node (ref "U3") (pin "10") (pinfunction "+IN_D_10") (pintype "input"))
    )
    (net (code "122") (name "unconnected-(U3--IN_D-Pad9)") (class "Default")
      (node (ref "U3") (pin "9") (pinfunction "-IN_D_9") (pintype "input"))
    )
    (net (code "123") (name "unconnected-(U3-OUT_C-Pad5)") (class "Default")
      (node (ref "U3") (pin "5") (pinfunction "OUT_C_5") (pintype "output"))
    )
    (net (code "124") (name "unconnected-(U3-OUT_D-Pad11)") (class "Default")
      (node (ref "U3") (pin "11") (pinfunction "OUT_D_11") (pintype "output"))
    )
  )
)
